# -V1.net
KiCad netlist of a schematic drawn in EasyEDA Pro
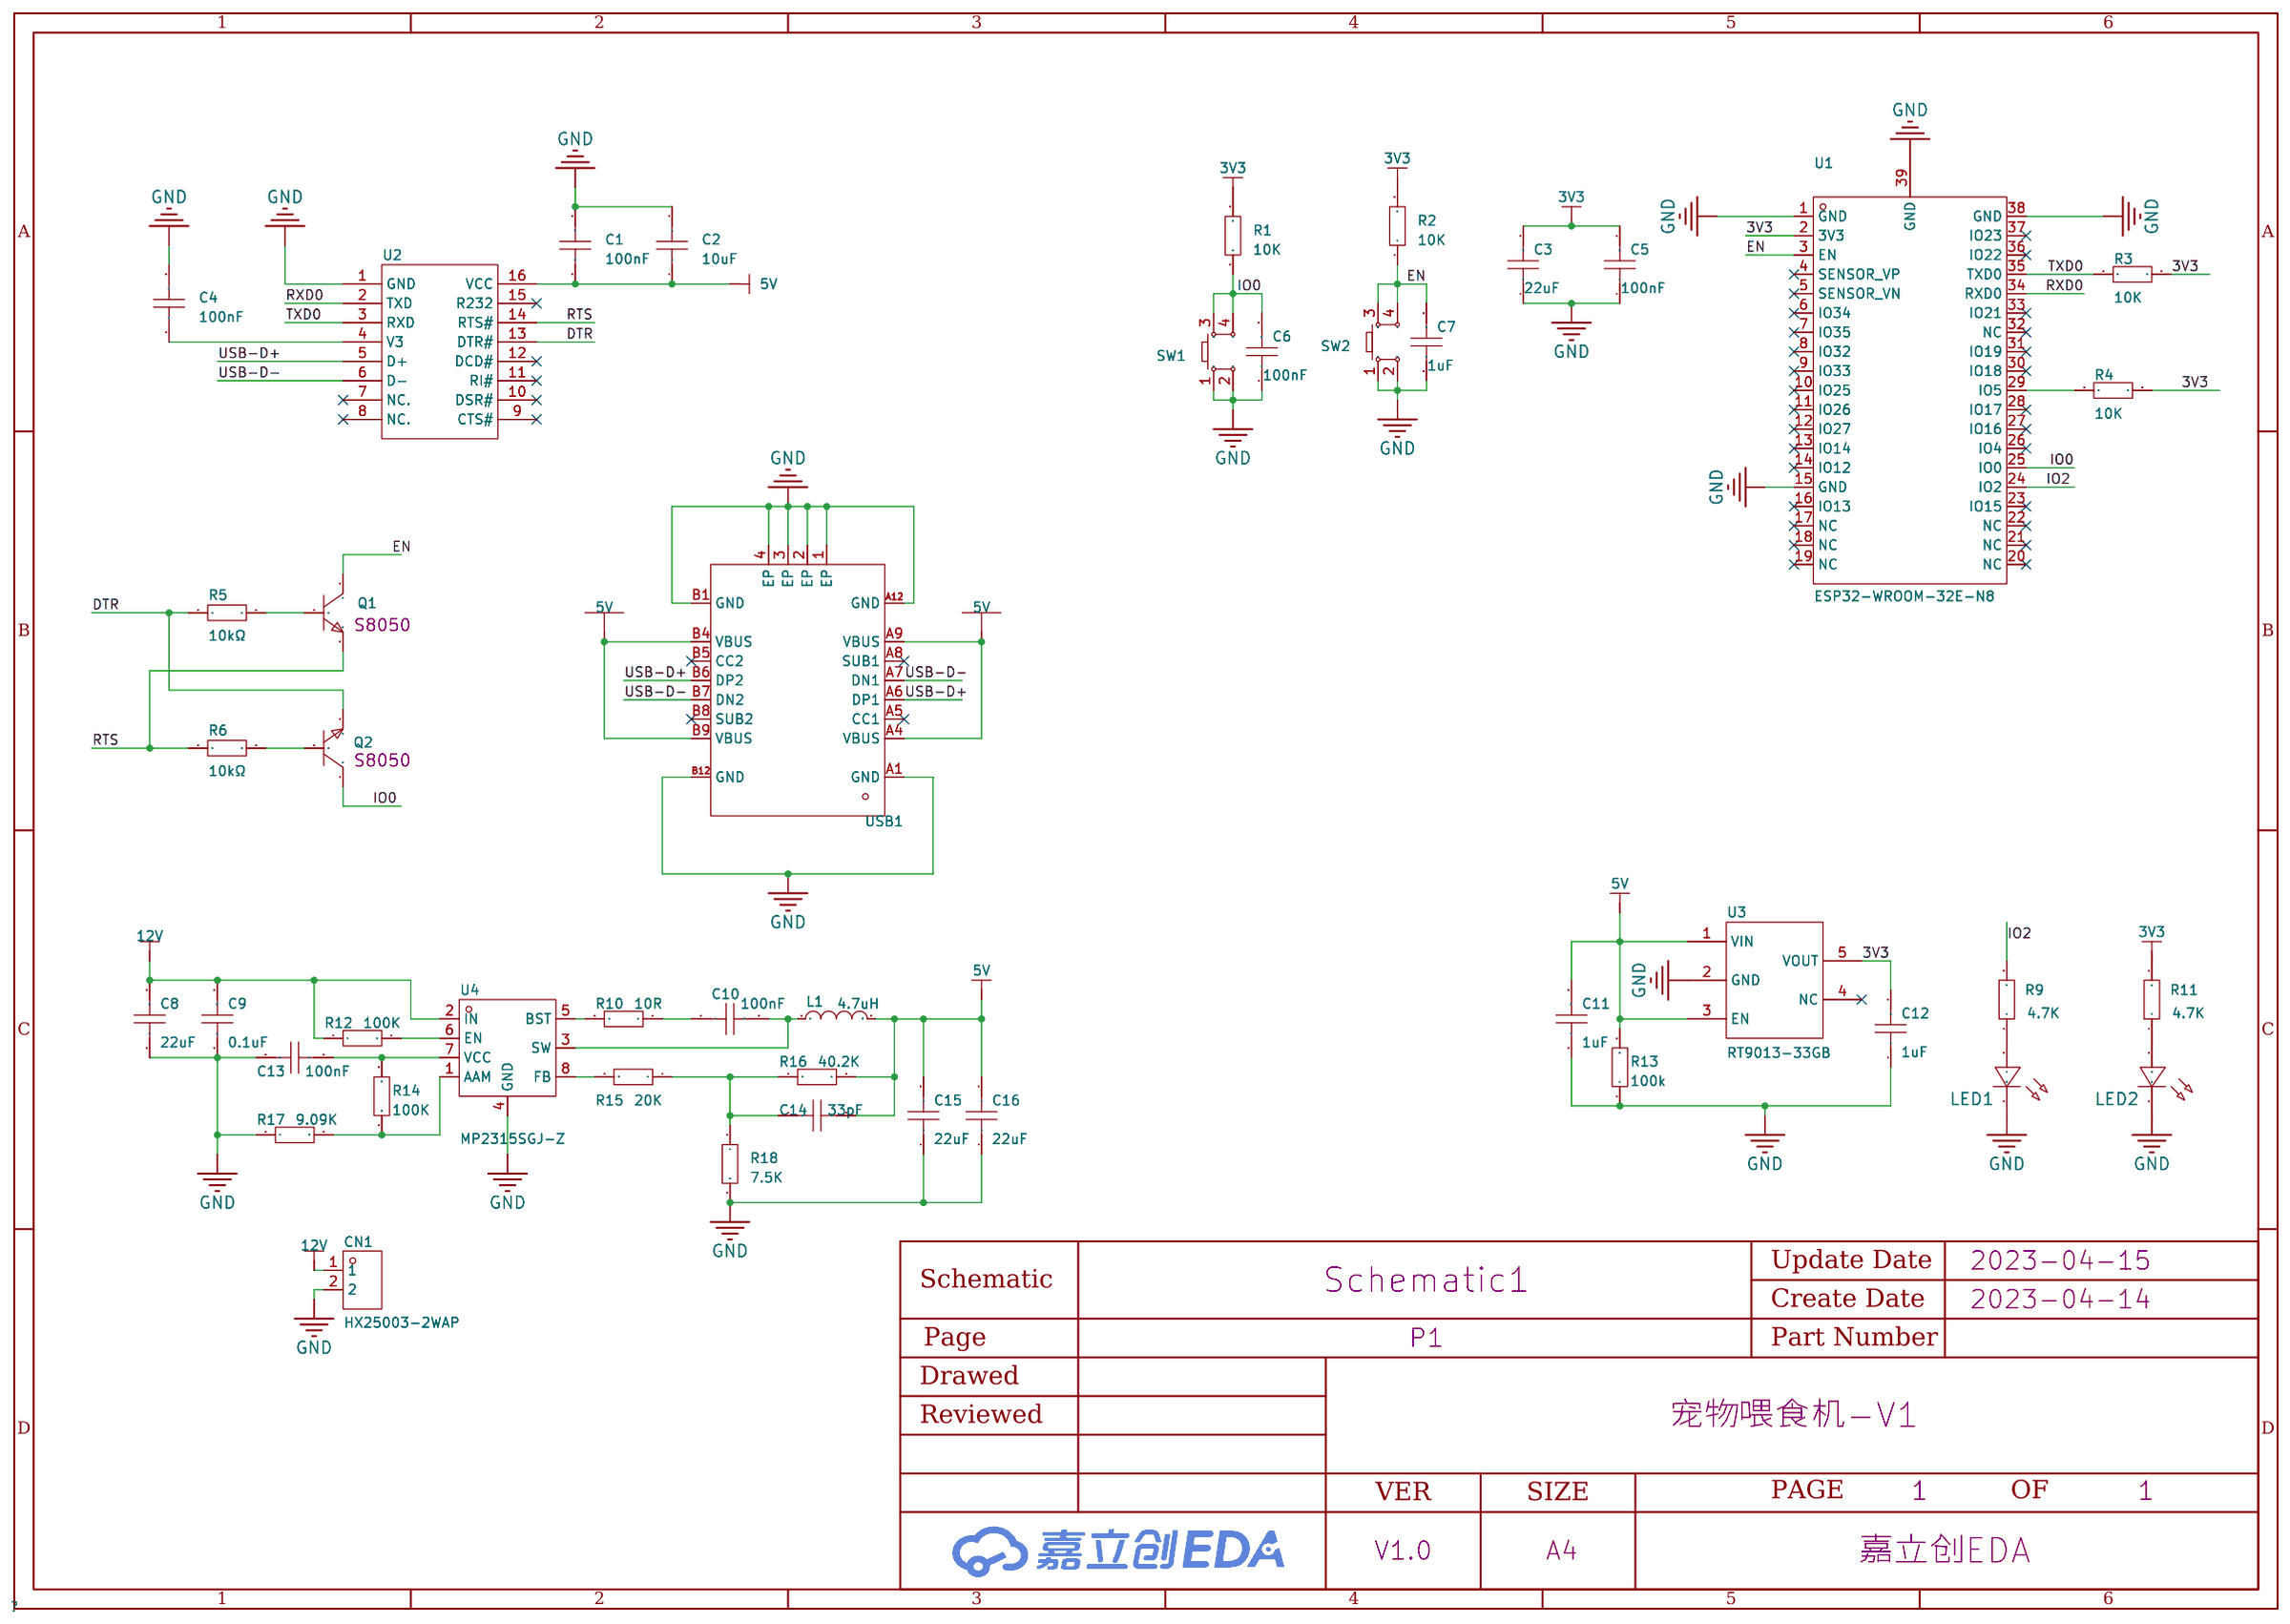
[diagram p0: schematic sheet]

(export (version "E")
  (design (tool "Eeschema 10.0.6"))
  (components
    (comp (ref "C1")
      (value "100nF")
      (footprint "easyedapro:C1206")
      (libsource (lib "easyedapro") (part "CapAcitance"))
    )
    (comp (ref "C2")
      (value "10uF")
      (footprint "easyedapro:C1206")
      (libsource (lib "easyedapro") (part "CapAcitance"))
    )
    (comp (ref "C3")
      (value "22uF")
      (footprint "easyedapro:C1206")
      (libsource (lib "easyedapro") (part "CapAcitance"))
    )
    (comp (ref "C4")
      (value "100nF")
      (footprint "easyedapro:C1206")
      (libsource (lib "easyedapro") (part "CapAcitance"))
    )
    (comp (ref "C5")
      (value "100nF")
      (footprint "easyedapro:C1206")
      (libsource (lib "easyedapro") (part "CapAcitance"))
    )
    (comp (ref "C6")
      (value "100nF")
      (footprint "easyedapro:C1206")
      (libsource (lib "easyedapro") (part "CapAcitance"))
    )
    (comp (ref "C7")
      (value "1uF")
      (footprint "easyedapro:C1206")
      (libsource (lib "easyedapro") (part "CapAcitance"))
    )
    (comp (ref "C8")
      (value "22uF")
      (footprint "easyedapro:C1206")
      (libsource (lib "easyedapro") (part "CapAcitance"))
    )
    (comp (ref "C9")
      (value "0.1uF")
      (footprint "easyedapro:C1206")
      (libsource (lib "easyedapro") (part "CapAcitance"))
    )
    (comp (ref "C10")
      (value "100nF")
      (footprint "easyedapro:C1206")
      (libsource (lib "easyedapro") (part "CapAcitance"))
    )
    (comp (ref "C11")
      (value "1uF")
      (footprint "easyedapro:C0603_1")
      (libsource (lib "easyedapro") (part "CapAcitance_1"))
    )
    (comp (ref "C12")
      (value "1uF")
      (footprint "easyedapro:C0603_1")
      (libsource (lib "easyedapro") (part "CapAcitance_1"))
    )
    (comp (ref "C13")
      (value "100nF")
      (footprint "easyedapro:C0402_NEW")
      (description "容值:100nF;精度:±10%;额定电压:16V;材质(温度系数):X7R;")
      (fields
        (field (name "Manufacturer Part") "CL05B104KO5NNNC")
        (field (name "Manufacturer") "SAMSUNG(三星)")
      )
      (libsource (lib "easyedapro") (part "C1210X7R475K630NT"))
    )
    (comp (ref "C14")
      (value "33pF")
      (footprint "easyedapro:C1206")
      (libsource (lib "easyedapro") (part "CapAcitance"))
    )
    (comp (ref "C15")
      (value "22uF")
      (footprint "easyedapro:C1206")
      (libsource (lib "easyedapro") (part "CapAcitance"))
    )
    (comp (ref "C16")
      (value "22uF")
      (footprint "easyedapro:C1206")
      (libsource (lib "easyedapro") (part "CapAcitance"))
    )
    (comp (ref "CN1")
      (value "HX25003-2WAP")
      (footprint "easyedapro:CONN-TH_2P-P2.50_HX25003-2WAP")
      (description "参考系列:XH;间距:2.5mm;插针结构:1x2P;排数:1;每排PIN数:2;行距:-;公母:公型插针;安装方式:弯插;额定电流:-;工作温度范围:-;")
      (fields (field (name "Manufacturer") "HX(红星)"))
      (libsource (lib "easyedapro") (part "HX25003-2WAP"))
    )
    (comp (ref "L1")
      (value "4.7uH")
      (footprint "easyedapro:IND-SMD_L7.3-W6.6")
      (description "电感值:4.7uH;精度:±20%;额定电流:5.5A;饱和电流(Isat):7A;")
      (fields (field (name "Manufacturer Part") "MCS0630-4R7MPY1") (field (name "Manufacturer") "PSA(信昌电陶)"))
      (libsource (lib "easyedapro") (part "MCS0630-4R7MPY1"))
    )
    (comp (ref "LED1")
      (value "~")
      (footprint "easyedapro:LED_0603")
      (libsource (lib "easyedapro") (part "LED_R"))
    )
    (comp (ref "LED2")
      (value "~")
      (footprint "easyedapro:LED_0603")
      (libsource (lib "easyedapro") (part "LED_R"))
    )
    (comp (ref "Q1")
      (value "~")
      (footprint "easyedapro:S8050_SOT-23")
      (fields (field (name "Manufacturer Part") "S8050"))
      (libsource (lib "easyedapro") (part "NPN"))
    )
    (comp (ref "Q2")
      (value "~")
      (footprint "easyedapro:S8050_SOT-23")
      (fields (field (name "Manufacturer Part") "S8050"))
      (libsource (lib "easyedapro") (part "NPN"))
    )
    (comp (ref "R1")
      (value "10K")
      (footprint "easyedapro:R0603")
      (libsource (lib "easyedapro") (part "电阻_1"))
    )
    (comp (ref "R2")
      (value "10K")
      (footprint "easyedapro:R0603")
      (libsource (lib "easyedapro") (part "电阻_1"))
    )
    (comp (ref "R3")
      (value "10K")
      (footprint "easyedapro:R0603")
      (libsource (lib "easyedapro") (part "电阻_1"))
    )
    (comp (ref "R4")
      (value "10K")
      (footprint "easyedapro:R0603")
      (libsource (lib "easyedapro") (part "电阻_1"))
    )
    (comp (ref "R5")
      (value "10kΩ")
      (footprint "easyedapro:R0402")
      (description "电阻类型:厚膜电阻;阻值:12kΩ;精度:±1%;功率:62.5mW;温度系数:±100ppm/°C;最大工作电压:50V;工作温度范围:-55°C~+155°C;")
      (fields
        (field (name "Manufacturer Part") "0402WGF1202TCE")
        (field (name "Manufacturer") "UNI-ROYAL(厚声)")
      )
      (libsource (lib "easyedapro") (part "电阻"))
    )
    (comp (ref "R6")
      (value "10kΩ")
      (footprint "easyedapro:R0402")
      (description "电阻类型:厚膜电阻;阻值:12kΩ;精度:±1%;功率:62.5mW;温度系数:±100ppm/°C;最大工作电压:50V;工作温度范围:-55°C~+155°C;")
      (fields
        (field (name "Manufacturer Part") "0402WGF1202TCE")
        (field (name "Manufacturer") "UNI-ROYAL(厚声)")
      )
      (libsource (lib "easyedapro") (part "电阻"))
    )
    (comp (ref "R9")
      (value "4.7K")
      (footprint "easyedapro:R0603")
      (libsource (lib "easyedapro") (part "电阻_1"))
    )
    (comp (ref "R10")
      (value "10R")
      (footprint "easyedapro:R0603")
      (libsource (lib "easyedapro") (part "电阻_1"))
    )
    (comp (ref "R11")
      (value "4.7K")
      (footprint "easyedapro:R0603")
      (libsource (lib "easyedapro") (part "电阻_1"))
    )
    (comp (ref "R12")
      (value "100K")
      (footprint "easyedapro:R0603")
      (libsource (lib "easyedapro") (part "电阻_1"))
    )
    (comp (ref "R13")
      (value "100k")
      (footprint "easyedapro:R0603")
      (libsource (lib "easyedapro") (part "电阻_1"))
    )
    (comp (ref "R14")
      (value "100K")
      (footprint "easyedapro:R0603")
      (libsource (lib "easyedapro") (part "电阻_1"))
    )
    (comp (ref "R15")
      (value "20K")
      (footprint "easyedapro:R0603")
      (libsource (lib "easyedapro") (part "电阻_1"))
    )
    (comp (ref "R16")
      (value "40.2K")
      (footprint "easyedapro:R0603")
      (libsource (lib "easyedapro") (part "电阻_1"))
    )
    (comp (ref "R17")
      (value "9.09K")
      (footprint "easyedapro:R0603")
      (libsource (lib "easyedapro") (part "电阻_1"))
    )
    (comp (ref "R18")
      (value "7.5K")
      (footprint "easyedapro:R0603")
      (libsource (lib "easyedapro") (part "电阻_1"))
    )
    (comp (ref "SW1")
      (value "~")
      (footprint "easyedapro:KEY-SMD_4P-L4.5-W4.5-P3.00-LS6.8")
      (libsource (lib "easyedapro") (part "轻触按键"))
    )
    (comp (ref "SW2")
      (value "~")
      (footprint "easyedapro:KEY-SMD_4P-L4.5-W4.5-P3.00-LS6.8")
      (libsource (lib "easyedapro") (part "轻触按键"))
    )
    (comp (ref "U1")
      (value "ESP32-WROOM-32E-N8")
      (footprint "easyedapro:WIFI-SMD_ESP32-WROOM-32E")
      (description "ESP32-WROOM-32E 集成 ESP32-D0WD-V3 芯片，具有?高的稳定性和安全性能。")
      (fields (field (name "Manufacturer") "ESPRESSIF(乐鑫)"))
      (libsource (lib "easyedapro") (part "ESP32-WROOM-32E(8MB)"))
    )
    (comp (ref "U2")
      (value "CH340C")
      (footprint "easyedapro:SOP-16_L10.0-W3.9-P1.27-LS6.0-BL")
      (description "类型:Transceiver;协议类别:USB 2.0;驱动器/接收器数:-;数据速率:2Mbps;")
      (fields (field (name "Manufacturer") "WCH(南京沁恒)"))
      (libsource (lib "easyedapro") (part "CH340C"))
    )
    (comp (ref "U3")
      (value "RT9013-33GB")
      (footprint "easyedapro:SOT-23-5_L3.0-W1.7-P0.95-LS2.8-BL")
      (fields (field (name "Manufacturer") "RICHTEK(立锜)"))
      (libsource (lib "easyedapro") (part "RT9013-33GB"))
    )
    (comp (ref "U4")
      (value "MP2315SGJ-Z")
      (footprint "easyedapro:TSOT-23-8_L2.9-W1.6-P0.65-LS2.8-BL")
      (libsource (lib "easyedapro") (part "MP2315SGJ-Z"))
    )
    (comp (ref "USB1")
      (value "~")
      (footprint "easyedapro:USB-C-SMD_KH-TYPE-C-16P_1")
      (description "Type-C母座 16PIN 立式四角贴板无压片")
      (fields
        (field (name "Manufacturer Part") "KH-TYPE-C-16P")
        (field (name "Manufacturer") "kinghelm(金航标)")
      )
      (libsource (lib "easyedapro") (part "KH-TYPE-C-16P_1"))
    )
  )
  (nets
    (net (code "1") (name "/DTR") (class "Default")
      (node (ref "Q2") (pin "2") (pinfunction "2_2") (pintype "unspecified"))
      (node (ref "R5") (pin "1") (pinfunction "1_1") (pintype "input"))
      (node (ref "U2") (pin "13") (pinfunction "DTR#_13") (pintype "input"))
    )
    (net (code "2") (name "/EN") (class "Default")
      (node (ref "C7") (pin "2") (pinfunction "2_2") (pintype "input"))
      (node (ref "Q1") (pin "3") (pinfunction "3_3") (pintype "unspecified"))
      (node (ref "R2") (pin "1") (pinfunction "1_1") (pintype "input"))
      (node (ref "SW2") (pin "3") (pinfunction "3_3") (pintype "input"))
      (node (ref "SW2") (pin "4") (pinfunction "4_4") (pintype "input"))
      (node (ref "U1") (pin "3") (pinfunction "EN_3") (pintype "input"))
    )
    (net (code "3") (name "/IO0") (class "Default")
      (node (ref "C6") (pin "2") (pinfunction "2_2") (pintype "input"))
      (node (ref "Q2") (pin "3") (pinfunction "3_3") (pintype "unspecified"))
      (node (ref "R1") (pin "1") (pinfunction "1_1") (pintype "input"))
      (node (ref "SW1") (pin "3") (pinfunction "3_3") (pintype "input"))
      (node (ref "SW1") (pin "4") (pinfunction "4_4") (pintype "input"))
      (node (ref "U1") (pin "25") (pinfunction "IO0_25") (pintype "input"))
    )
    (net (code "4") (name "/IO2") (class "Default")
      (node (ref "R9") (pin "2") (pinfunction "2_2") (pintype "input"))
      (node (ref "U1") (pin "24") (pinfunction "IO2_24") (pintype "input"))
    )
    (net (code "5") (name "/RTS") (class "Default")
      (node (ref "Q1") (pin "2") (pinfunction "2_2") (pintype "unspecified"))
      (node (ref "R6") (pin "1") (pinfunction "1_1") (pintype "input"))
      (node (ref "U2") (pin "14") (pinfunction "RTS#_14") (pintype "input"))
    )
    (net (code "6") (name "/RXD0") (class "Default")
      (node (ref "U1") (pin "34") (pinfunction "RXD0_34") (pintype "input"))
      (node (ref "U2") (pin "2") (pinfunction "TXD_2") (pintype "input"))
    )
    (net (code "7") (name "/TXD0") (class "Default")
      (node (ref "R3") (pin "2") (pinfunction "2_2") (pintype "input"))
      (node (ref "U1") (pin "35") (pinfunction "TXD0_35") (pintype "input"))
      (node (ref "U2") (pin "3") (pinfunction "RXD_3") (pintype "input"))
    )
    (net (code "8") (name "/USB-D+") (class "Default")
      (node (ref "U2") (pin "5") (pinfunction "D+_5") (pintype "input"))
      (node (ref "USB1") (pin "A6") (pinfunction "DP1_A6") (pintype "input"))
      (node (ref "USB1") (pin "B6") (pinfunction "DP2_B6") (pintype "input"))
    )
    (net (code "9") (name "/USB-D-") (class "Default")
      (node (ref "U2") (pin "6") (pinfunction "D-_6") (pintype "input"))
      (node (ref "USB1") (pin "A7") (pinfunction "DN1_A7") (pintype "input"))
      (node (ref "USB1") (pin "B7") (pinfunction "DN2_B7") (pintype "input"))
    )
    (net (code "10") (name "3V3") (class "Default")
      (node (ref "C12") (pin "2") (pinfunction "2_2") (pintype "input"))
      (node (ref "C3") (pin "2") (pinfunction "2_2") (pintype "input"))
      (node (ref "C5") (pin "2") (pinfunction "2_2") (pintype "input"))
      (node (ref "R1") (pin "2") (pinfunction "2_2") (pintype "input"))
      (node (ref "R11") (pin "2") (pinfunction "2_2") (pintype "input"))
      (node (ref "R2") (pin "2") (pinfunction "2_2") (pintype "input"))
      (node (ref "R3") (pin "1") (pinfunction "1_1") (pintype "input"))
      (node (ref "R4") (pin "1") (pinfunction "1_1") (pintype "input"))
      (node (ref "U1") (pin "2") (pinfunction "3V3_2") (pintype "input"))
      (node (ref "U3") (pin "5") (pinfunction "VOUT_5") (pintype "input"))
    )
    (net (code "11") (name "5V") (class "Default")
      (node (ref "C1") (pin "1") (pinfunction "1_1") (pintype "input"))
      (node (ref "C11") (pin "2") (pinfunction "2_2") (pintype "input"))
      (node (ref "C14") (pin "2") (pinfunction "2_2") (pintype "input"))
      (node (ref "C15") (pin "2") (pinfunction "2_2") (pintype "input"))
      (node (ref "C16") (pin "2") (pinfunction "2_2") (pintype "input"))
      (node (ref "C2") (pin "1") (pinfunction "1_1") (pintype "input"))
      (node (ref "L1") (pin "2") (pinfunction "2_2") (pintype "input"))
      (node (ref "R13") (pin "2") (pinfunction "2_2") (pintype "input"))
      (node (ref "R16") (pin "2") (pinfunction "2_2") (pintype "input"))
      (node (ref "U2") (pin "16") (pinfunction "VCC_16") (pintype "input"))
      (node (ref "U3") (pin "1") (pinfunction "VIN_1") (pintype "input"))
      (node (ref "U3") (pin "3") (pinfunction "EN_3") (pintype "input"))
      (node (ref "USB1") (pin "A4") (pinfunction "VBUS_A4") (pintype "input"))
      (node (ref "USB1") (pin "A9") (pinfunction "VBUS_A9") (pintype "input"))
      (node (ref "USB1") (pin "B4") (pinfunction "VBUS_B4") (pintype "input"))
      (node (ref "USB1") (pin "B9") (pinfunction "VBUS_B9") (pintype "input"))
    )
    (net (code "12") (name "12V") (class "Default")
      (node (ref "C8") (pin "2") (pinfunction "2_2") (pintype "input"))
      (node (ref "C9") (pin "2") (pinfunction "2_2") (pintype "input"))
      (node (ref "CN1") (pin "1") (pinfunction "1_1") (pintype "input"))
      (node (ref "R12") (pin "1") (pinfunction "1_1") (pintype "input"))
      (node (ref "U4") (pin "2") (pinfunction "IN_2") (pintype "input"))
    )
    (net (code "13") (name "GND") (class "Default")
      (node (ref "C1") (pin "2") (pinfunction "2_2") (pintype "input"))
      (node (ref "C11") (pin "1") (pinfunction "1_1") (pintype "input"))
      (node (ref "C12") (pin "1") (pinfunction "1_1") (pintype "input"))
      (node (ref "C13") (pin "2") (pinfunction "2_2") (pintype "input"))
      (node (ref "C15") (pin "1") (pinfunction "1_1") (pintype "input"))
      (node (ref "C16") (pin "1") (pinfunction "1_1") (pintype "input"))
      (node (ref "C2") (pin "2") (pinfunction "2_2") (pintype "input"))
      (node (ref "C3") (pin "1") (pinfunction "1_1") (pintype "input"))
      (node (ref "C4") (pin "2") (pinfunction "2_2") (pintype "input"))
      (node (ref "C5") (pin "1") (pinfunction "1_1") (pintype "input"))
      (node (ref "C6") (pin "1") (pinfunction "1_1") (pintype "input"))
      (node (ref "C7") (pin "1") (pinfunction "1_1") (pintype "input"))
      (node (ref "C8") (pin "1") (pinfunction "1_1") (pintype "input"))
      (node (ref "C9") (pin "1") (pinfunction "1_1") (pintype "input"))
      (node (ref "CN1") (pin "2") (pinfunction "2_2") (pintype "input"))
      (node (ref "LED1") (pin "1") (pinfunction "C_1") (pintype "input"))
      (node (ref "LED2") (pin "1") (pinfunction "C_1") (pintype "input"))
      (node (ref "R13") (pin "1") (pinfunction "1_1") (pintype "input"))
      (node (ref "R17") (pin "1") (pinfunction "1_1") (pintype "input"))
      (node (ref "R18") (pin "2") (pinfunction "2_2") (pintype "input"))
      (node (ref "SW1") (pin "1") (pinfunction "1_1") (pintype "input"))
      (node (ref "SW1") (pin "2") (pinfunction "2_2") (pintype "input"))
      (node (ref "SW2") (pin "1") (pinfunction "1_1") (pintype "input"))
      (node (ref "SW2") (pin "2") (pinfunction "2_2") (pintype "input"))
      (node (ref "U1") (pin "1") (pinfunction "GND_1") (pintype "input"))
      (node (ref "U1") (pin "15") (pinfunction "GND_15") (pintype "input"))
      (node (ref "U1") (pin "38") (pinfunction "GND_38") (pintype "input"))
      (node (ref "U1") (pin "39") (pinfunction "GND_39") (pintype "input"))
      (node (ref "U2") (pin "1") (pinfunction "GND_1") (pintype "input"))
      (node (ref "U3") (pin "2") (pinfunction "GND_2") (pintype "input"))
      (node (ref "U4") (pin "4") (pinfunction "GND_4") (pintype "input"))
      (node (ref "USB1") (pin "1") (pinfunction "EP_1") (pintype "input"))
      (node (ref "USB1") (pin "2") (pinfunction "EP_2") (pintype "input"))
      (node (ref "USB1") (pin "3") (pinfunction "EP_3") (pintype "input"))
      (node (ref "USB1") (pin "4") (pinfunction "EP_4") (pintype "input"))
      (node (ref "USB1") (pin "A1") (pinfunction "GND_A1") (pintype "input"))
      (node (ref "USB1") (pin "A12") (pinfunction "GND_A12") (pintype "input"))
      (node (ref "USB1") (pin "B1") (pinfunction "GND_B1") (pintype "input"))
      (node (ref "USB1") (pin "B12") (pinfunction "GND_B12") (pintype "input"))
    )
    (net (code "14") (name "Net-(C10-Pad1)") (class "Default")
      (node (ref "C10") (pin "1") (pinfunction "1_1") (pintype "input"))
      (node (ref "R10") (pin "1") (pinfunction "1_1") (pintype "input"))
    )
    (net (code "15") (name "Net-(C14-Pad1)") (class "Default")
      (node (ref "C14") (pin "1") (pinfunction "1_1") (pintype "input"))
      (node (ref "R15") (pin "1") (pinfunction "1_1") (pintype "input"))
      (node (ref "R16") (pin "1") (pinfunction "1_1") (pintype "input"))
      (node (ref "R18") (pin "1") (pinfunction "1_1") (pintype "input"))
    )
    (net (code "16") (name "Net-(LED1-A)") (class "Default")
      (node (ref "LED1") (pin "2") (pinfunction "A_2") (pintype "input"))
      (node (ref "R9") (pin "1") (pinfunction "1_1") (pintype "input"))
    )
    (net (code "17") (name "Net-(LED2-A)") (class "Default")
      (node (ref "LED2") (pin "2") (pinfunction "A_2") (pintype "input"))
      (node (ref "R11") (pin "1") (pinfunction "1_1") (pintype "input"))
    )
    (net (code "18") (name "Net-(Q1-Pad1)") (class "Default")
      (node (ref "Q1") (pin "1") (pinfunction "1_1") (pintype "unspecified"))
      (node (ref "R5") (pin "2") (pinfunction "2_2") (pintype "input"))
    )
    (net (code "19") (name "Net-(Q2-Pad1)") (class "Default")
      (node (ref "Q2") (pin "1") (pinfunction "1_1") (pintype "unspecified"))
      (node (ref "R6") (pin "2") (pinfunction "2_2") (pintype "input"))
    )
    (net (code "20") (name "Net-(U1-IO5)") (class "Default")
      (node (ref "R4") (pin "2") (pinfunction "2_2") (pintype "input"))
      (node (ref "U1") (pin "29") (pinfunction "IO5_29") (pintype "input"))
    )
    (net (code "21") (name "Net-(U2-V3)") (class "Default")
      (node (ref "C4") (pin "1") (pinfunction "1_1") (pintype "input"))
      (node (ref "U2") (pin "4") (pinfunction "V3_4") (pintype "input"))
    )
    (net (code "22") (name "Net-(U4-AAM)") (class "Default")
      (node (ref "R14") (pin "1") (pinfunction "1_1") (pintype "input"))
      (node (ref "R17") (pin "2") (pinfunction "2_2") (pintype "input"))
      (node (ref "U4") (pin "1") (pinfunction "AAM_1") (pintype "input"))
    )
    (net (code "23") (name "Net-(U4-BST)") (class "Default")
      (node (ref "R10") (pin "2") (pinfunction "2_2") (pintype "input"))
      (node (ref "U4") (pin "5") (pinfunction "BST_5") (pintype "input"))
    )
    (net (code "24") (name "Net-(U4-EN)") (class "Default")
      (node (ref "R12") (pin "2") (pinfunction "2_2") (pintype "input"))
      (node (ref "U4") (pin "6") (pinfunction "EN_6") (pintype "input"))
    )
    (net (code "25") (name "Net-(U4-FB)") (class "Default")
      (node (ref "R15") (pin "2") (pinfunction "2_2") (pintype "input"))
      (node (ref "U4") (pin "8") (pinfunction "FB_8") (pintype "input"))
    )
    (net (code "26") (name "Net-(U4-SW)") (class "Default")
      (node (ref "C10") (pin "2") (pinfunction "2_2") (pintype "input"))
      (node (ref "L1") (pin "1") (pinfunction "1_1") (pintype "input"))
      (node (ref "U4") (pin "3") (pinfunction "SW_3") (pintype "input"))
    )
    (net (code "27") (name "Net-(U4-VCC)") (class "Default")
      (node (ref "C13") (pin "1") (pinfunction "1_1") (pintype "input"))
      (node (ref "R14") (pin "2") (pinfunction "2_2") (pintype "input"))
      (node (ref "U4") (pin "7") (pinfunction "VCC_7") (pintype "input"))
    )
    (net (code "28") (name "unconnected-(U1-IO4-Pad26)") (class "Default")
      (node (ref "U1") (pin "26") (pinfunction "IO4_26") (pintype "input+no_connect"))
    )
    (net (code "29") (name "unconnected-(U1-IO12-Pad14)") (class "Default")
      (node (ref "U1") (pin "14") (pinfunction "IO12_14") (pintype "input+no_connect"))
    )
    (net (code "30") (name "unconnected-(U1-IO13-Pad16)") (class "Default")
      (node (ref "U1") (pin "16") (pinfunction "IO13_16") (pintype "input+no_connect"))
    )
    (net (code "31") (name "unconnected-(U1-IO14-Pad13)") (class "Default")
      (node (ref "U1") (pin "13") (pinfunction "IO14_13") (pintype "input+no_connect"))
    )
    (net (code "32") (name "unconnected-(U1-IO15-Pad23)") (class "Default")
      (node (ref "U1") (pin "23") (pinfunction "IO15_23") (pintype "input+no_connect"))
    )
    (net (code "33") (name "unconnected-(U1-IO16-Pad27)") (class "Default")
      (node (ref "U1") (pin "27") (pinfunction "IO16_27") (pintype "input+no_connect"))
    )
    (net (code "34") (name "unconnected-(U1-IO17-Pad28)") (class "Default")
      (node (ref "U1") (pin "28") (pinfunction "IO17_28") (pintype "input+no_connect"))
    )
    (net (code "35") (name "unconnected-(U1-IO18-Pad30)") (class "Default")
      (node (ref "U1") (pin "30") (pinfunction "IO18_30") (pintype "input+no_connect"))
    )
    (net (code "36") (name "unconnected-(U1-IO19-Pad31)") (class "Default")
      (node (ref "U1") (pin "31") (pinfunction "IO19_31") (pintype "input+no_connect"))
    )
    (net (code "37") (name "unconnected-(U1-IO21-Pad33)") (class "Default")
      (node (ref "U1") (pin "33") (pinfunction "IO21_33") (pintype "input+no_connect"))
    )
    (net (code "38") (name "unconnected-(U1-IO22-Pad36)") (class "Default")
      (node (ref "U1") (pin "36") (pinfunction "IO22_36") (pintype "input+no_connect"))
    )
    (net (code "39") (name "unconnected-(U1-IO23-Pad37)") (class "Default")
      (node (ref "U1") (pin "37") (pinfunction "IO23_37") (pintype "input+no_connect"))
    )
    (net (code "40") (name "unconnected-(U1-IO25-Pad10)") (class "Default")
      (node (ref "U1") (pin "10") (pinfunction "IO25_10") (pintype "input+no_connect"))
    )
    (net (code "41") (name "unconnected-(U1-IO26-Pad11)") (class "Default")
      (node (ref "U1") (pin "11") (pinfunction "IO26_11") (pintype "input+no_connect"))
    )
    (net (code "42") (name "unconnected-(U1-IO27-Pad12)") (class "Default")
      (node (ref "U1") (pin "12") (pinfunction "IO27_12") (pintype "input+no_connect"))
    )
    (net (code "43") (name "unconnected-(U1-IO32-Pad8)") (class "Default")
      (node (ref "U1") (pin "8") (pinfunction "IO32_8") (pintype "input+no_connect"))
    )
    (net (code "44") (name "unconnected-(U1-IO33-Pad9)") (class "Default")
      (node (ref "U1") (pin "9") (pinfunction "IO33_9") (pintype "input+no_connect"))
    )
    (net (code "45") (name "unconnected-(U1-IO34-Pad6)") (class "Default")
      (node (ref "U1") (pin "6") (pinfunction "IO34_6") (pintype "input+no_connect"))
    )
    (net (code "46") (name "unconnected-(U1-IO35-Pad7)") (class "Default")
      (node (ref "U1") (pin "7") (pinfunction "IO35_7") (pintype "input+no_connect"))
    )
    (net (code "47") (name "unconnected-(U1-NC-Pad17)") (class "Default")
      (node (ref "U1") (pin "17") (pinfunction "NC_17") (pintype "input+no_connect"))
    )
    (net (code "48") (name "unconnected-(U1-NC-Pad18)") (class "Default")
      (node (ref "U1") (pin "18") (pinfunction "NC_18") (pintype "input+no_connect"))
    )
    (net (code "49") (name "unconnected-(U1-NC-Pad19)") (class "Default")
      (node (ref "U1") (pin "19") (pinfunction "NC_19") (pintype "input+no_connect"))
    )
    (net (code "50") (name "unconnected-(U1-NC-Pad20)") (class "Default")
      (node (ref "U1") (pin "20") (pinfunction "NC_20") (pintype "input+no_connect"))
    )
    (net (code "51") (name "unconnected-(U1-NC-Pad21)") (class "Default")
      (node (ref "U1") (pin "21") (pinfunction "NC_21") (pintype "input+no_connect"))
    )
    (net (code "52") (name "unconnected-(U1-NC-Pad22)") (class "Default")
      (node (ref "U1") (pin "22") (pinfunction "NC_22") (pintype "input+no_connect"))
    )
    (net (code "53") (name "unconnected-(U1-NC-Pad32)") (class "Default")
      (node (ref "U1") (pin "32") (pinfunction "NC_32") (pintype "input+no_connect"))
    )
    (net (code "54") (name "unconnected-(U1-SENSOR_VN-Pad5)") (class "Default")
      (node (ref "U1") (pin "5") (pinfunction "SENSOR_VN_5") (pintype "input+no_connect"))
    )
    (net (code "55") (name "unconnected-(U1-SENSOR_VP-Pad4)") (class "Default")
      (node (ref "U1") (pin "4") (pinfunction "SENSOR_VP_4") (pintype "input+no_connect"))
    )
    (net (code "56") (name "unconnected-(U2-CTS#-Pad9)") (class "Default")
      (node (ref "U2") (pin "9") (pinfunction "CTS#_9") (pintype "input+no_connect"))
    )
    (net (code "57") (name "unconnected-(U2-DCD#-Pad12)") (class "Default")
      (node (ref "U2") (pin "12") (pinfunction "DCD#_12") (pintype "input+no_connect"))
    )
    (net (code "58") (name "unconnected-(U2-DSR#-Pad10)") (class "Default")
      (node (ref "U2") (pin "10") (pinfunction "DSR#_10") (pintype "input+no_connect"))
    )
    (net (code "59") (name "unconnected-(U2-NC.-Pad7)") (class "Default")
      (node (ref "U2") (pin "7") (pinfunction "NC._7") (pintype "input+no_connect"))
    )
    (net (code "60") (name "unconnected-(U2-NC.-Pad8)") (class "Default")
      (node (ref "U2") (pin "8") (pinfunction "NC._8") (pintype "input+no_connect"))
    )
    (net (code "61") (name "unconnected-(U2-R232-Pad15)") (class "Default")
      (node (ref "U2") (pin "15") (pinfunction "R232_15") (pintype "input+no_connect"))
    )
    (net (code "62") (name "unconnected-(U2-RI#-Pad11)") (class "Default")
      (node (ref "U2") (pin "11") (pinfunction "RI#_11") (pintype "input+no_connect"))
    )
    (net (code "63") (name "unconnected-(U3-NC-Pad4)") (class "Default")
      (node (ref "U3") (pin "4") (pinfunction "NC_4") (pintype "input+no_connect"))
    )
    (net (code "64") (name "unconnected-(USB1-CC1-PadA5)") (class "Default")
      (node (ref "USB1") (pin "A5") (pinfunction "CC1_A5") (pintype "input+no_connect"))
    )
    (net (code "65") (name "unconnected-(USB1-CC2-PadB5)") (class "Default")
      (node (ref "USB1") (pin "B5") (pinfunction "CC2_B5") (pintype "input+no_connect"))
    )
    (net (code "66") (name "unconnected-(USB1-SUB1-PadA8)") (class "Default")
      (node (ref "USB1") (pin "A8") (pinfunction "SUB1_A8") (pintype "input+no_connect"))
    )
    (net (code "67") (name "unconnected-(USB1-SUB2-PadB8)") (class "Default")
      (node (ref "USB1") (pin "B8") (pinfunction "SUB2_B8") (pintype "input+no_connect"))
    )
  )
)
